# 1-Schematic_SmartPlugV2.net
KiCad netlist of a schematic drawn in EasyEDA
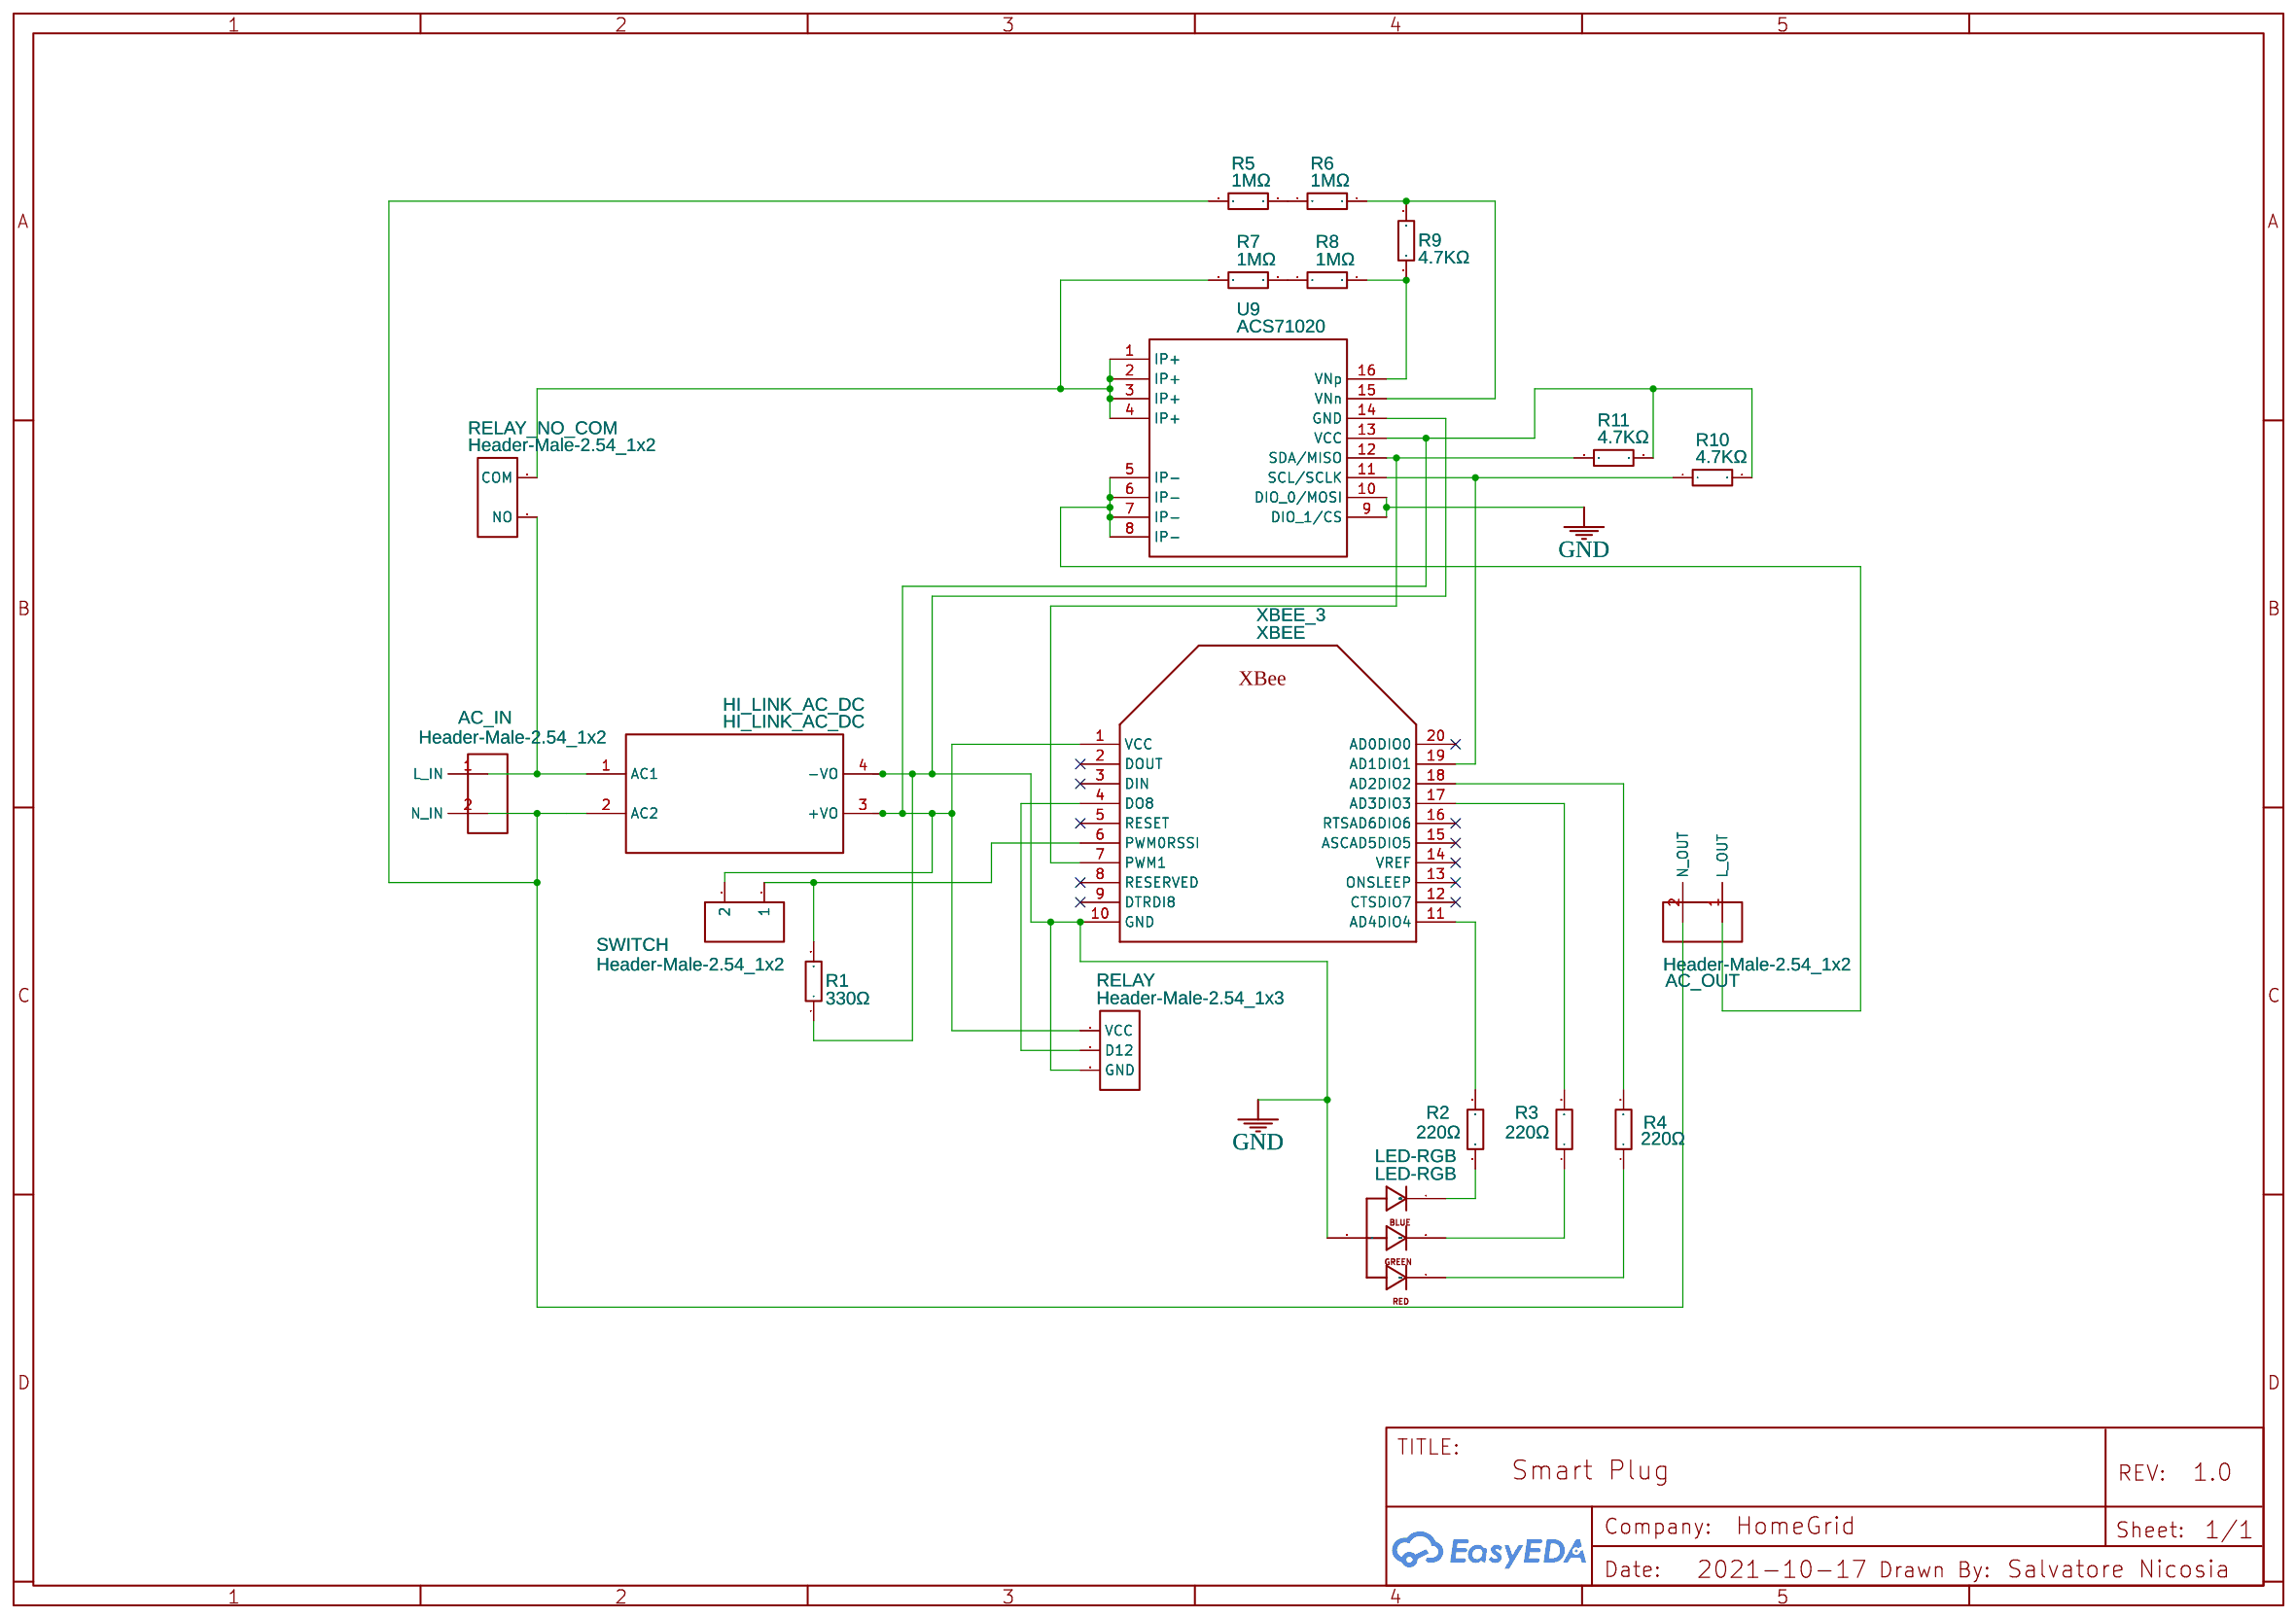
[diagram p0: schematic sheet]

(export (version "E")
  (design (tool "Eeschema 10.0.6"))
  (components
    (comp (ref "AC_IN") (value "Header-Male-2.54_1x2") (libsource (lib "") (part "DC Terminals (2)_1")))
    (comp (ref "AC_OUT") (value "Header-Male-2.54_1x2") (libsource (lib "") (part "DC Terminals (2)")))
    (comp (ref "HI_LINK_AC_DC") (value "HI_LINK_AC_DC") (libsource (lib "") (part "HI_LINK_AC_DC")))
    (comp (ref "LED-RGB") (value "LED-RGB") (libsource (lib "") (part "LED-RGB-CA-THRUCLEAR")))
    (comp (ref "R1") (value "330Ω") (libsource (lib "") (part "resistor 1k_2")))
    (comp (ref "R2") (value "220Ω") (libsource (lib "") (part "resistor 1k_2")))
    (comp (ref "R3") (value "220Ω") (libsource (lib "") (part "resistor 1k_2")))
    (comp (ref "R4") (value "220Ω") (libsource (lib "") (part "resistor 1k_2")))
    (comp (ref "R5") (value "1MΩ") (libsource (lib "") (part "resistor 1k")))
    (comp (ref "R6") (value "1MΩ") (libsource (lib "") (part "resistor 1k")))
    (comp (ref "R7") (value "1MΩ") (libsource (lib "") (part "resistor 1k")))
    (comp (ref "R8") (value "1MΩ") (libsource (lib "") (part "resistor 1k")))
    (comp (ref "R9") (value "4.7KΩ") (libsource (lib "") (part "resistor 1k_2")))
    (comp (ref "R10") (value "4.7KΩ") (libsource (lib "") (part "resistor 1k_1")))
    (comp (ref "R11") (value "4.7KΩ") (libsource (lib "") (part "resistor 1k_1")))
    (comp (ref "RELAY")
      (value "Header-Male-2.54_1x3")
      (fields
        (field (name "BOM_Manufacturer Part") "Header2.54mm 1*3P")
        (field (name "BOM_Supplier Part") "C49257")
      )
      (libsource (lib "") (part "Header-Male-2.54_1x3"))
    )
    (comp (ref "RELAY_NO_COM")
      (value "Header-Male-2.54_1x2")
      (fields (field (name "BOM_Manufacturer Part") "826629-2") (field (name "BOM_Supplier Part") "C86471"))
      (libsource (lib "") (part "Header-Male-2.54_1x2"))
    )
    (comp (ref "SWITCH")
      (value "Header-Male-2.54_1x2")
      (fields (field (name "BOM_Manufacturer Part") "826629-2") (field (name "BOM_Supplier Part") "C86471"))
      (libsource (lib "") (part "Header-Male-2.54_1x2_1"))
    )
    (comp (ref "U9")
      (value "ACS71020")
      (fields
        (field (name "BOM_Manufacturer Part") "ACS71020KMABTR-090B3-I2C")
        (field (name "BOM_Supplier Part") "620-1998-1-ND")
      )
      (libsource (lib "") (part "ACS71020"))
    )
    (comp (ref "XBEE_3") (value "XBEE") (libsource (lib "") (part "XBEE")))
  )
  (nets
    (net (code "1") (name "GND") (class "Default")
      (node (ref "HI_LINK_AC_DC") (pin "4") (pinfunction "-VO_4") (pintype "unspecified"))
      (node (ref "LED-RGB") (pin "2") (pinfunction "ANODE_2") (pintype "unspecified"))
      (node (ref "R1") (pin "1") (pinfunction "1_1") (pintype "unspecified"))
      (node (ref "RELAY") (pin "3") (pinfunction "GND_3") (pintype "input"))
      (node (ref "U9") (pin "10") (pinfunction "DIO_0/MOSI_10") (pintype "unspecified"))
      (node (ref "U9") (pin "14") (pinfunction "GND_14") (pintype "unspecified"))
      (node (ref "U9") (pin "9") (pinfunction "DIO_1/CS_9") (pintype "unspecified"))
      (node (ref "XBEE_3") (pin "10") (pinfunction "GND_10") (pintype "unspecified"))
    )
    (net (code "2") (name "Net-(AC_IN-L_IN)") (class "Default")
      (node (ref "AC_IN") (pin "1") (pinfunction "L_IN_1") (pintype "unspecified"))
      (node (ref "HI_LINK_AC_DC") (pin "1") (pinfunction "AC1_1") (pintype "unspecified"))
      (node (ref "RELAY_NO_COM") (pin "1") (pinfunction "NO_1") (pintype "unspecified"))
    )
    (net (code "3") (name "Net-(AC_IN-N_IN)") (class "Default")
      (node (ref "AC_IN") (pin "2") (pinfunction "N_IN_2") (pintype "unspecified"))
      (node (ref "AC_OUT") (pin "2") (pinfunction "N_OUT_2") (pintype "unspecified"))
      (node (ref "HI_LINK_AC_DC") (pin "2") (pinfunction "AC2_2") (pintype "unspecified"))
      (node (ref "R5") (pin "2") (pinfunction "2_2") (pintype "unspecified"))
    )
    (net (code "4") (name "Net-(AC_OUT-L_OUT)") (class "Default")
      (node (ref "AC_OUT") (pin "1") (pinfunction "L_OUT_1") (pintype "unspecified"))
      (node (ref "U9") (pin "5") (pinfunction "IP-_5") (pintype "unspecified"))
      (node (ref "U9") (pin "6") (pinfunction "IP-_6") (pintype "unspecified"))
      (node (ref "U9") (pin "7") (pinfunction "IP-_7") (pintype "unspecified"))
      (node (ref "U9") (pin "8") (pinfunction "IP-_8") (pintype "unspecified"))
    )
    (net (code "5") (name "Net-(HI_LINK_AC_DC-+VO)") (class "Default")
      (node (ref "HI_LINK_AC_DC") (pin "3") (pinfunction "+VO_3") (pintype "unspecified"))
      (node (ref "R10") (pin "2") (pinfunction "2_2") (pintype "unspecified"))
      (node (ref "R11") (pin "2") (pinfunction "2_2") (pintype "unspecified"))
      (node (ref "RELAY") (pin "1") (pinfunction "VCC_1") (pintype "input"))
      (node (ref "SWITCH") (pin "2") (pinfunction "2_2") (pintype "unspecified"))
      (node (ref "U9") (pin "13") (pinfunction "VCC_13") (pintype "unspecified"))
      (node (ref "XBEE_3") (pin "1") (pinfunction "VCC_1") (pintype "unspecified"))
    )
    (net (code "6") (name "Net-(LED-RGB-BLUE_CATHODE)") (class "Default")
      (node (ref "LED-RGB") (pin "4") (pinfunction "BLUE_CATHODE_4") (pintype "unspecified"))
      (node (ref "R2") (pin "1") (pinfunction "1_1") (pintype "unspecified"))
    )
    (net (code "7") (name "Net-(LED-RGB-GREEN_CATHODE)") (class "Default")
      (node (ref "LED-RGB") (pin "3") (pinfunction "GREEN_CATHODE_3") (pintype "unspecified"))
      (node (ref "R3") (pin "1") (pinfunction "1_1") (pintype "unspecified"))
    )
    (net (code "8") (name "Net-(LED-RGB-RED_CATHODE)") (class "Default")
      (node (ref "LED-RGB") (pin "1") (pinfunction "RED_CATHODE_1") (pintype "unspecified"))
      (node (ref "R4") (pin "1") (pinfunction "1_1") (pintype "unspecified"))
    )
    (net (code "9") (name "Net-(R5-Pad1)") (class "Default")
      (node (ref "R5") (pin "1") (pinfunction "1_1") (pintype "unspecified"))
      (node (ref "R6") (pin "2") (pinfunction "2_2") (pintype "unspecified"))
    )
    (net (code "10") (name "Net-(R7-Pad1)") (class "Default")
      (node (ref "R7") (pin "1") (pinfunction "1_1") (pintype "unspecified"))
      (node (ref "R8") (pin "2") (pinfunction "2_2") (pintype "unspecified"))
    )
    (net (code "11") (name "Net-(RELAY-D12)") (class "Default")
      (node (ref "RELAY") (pin "2") (pinfunction "D12_2") (pintype "input"))
      (node (ref "XBEE_3") (pin "4") (pinfunction "DO8_4") (pintype "output"))
    )
    (net (code "12") (name "Net-(RELAY_NO_COM-COM)") (class "Default")
      (node (ref "R7") (pin "2") (pinfunction "2_2") (pintype "unspecified"))
      (node (ref "RELAY_NO_COM") (pin "2") (pinfunction "COM_2") (pintype "unspecified"))
      (node (ref "U9") (pin "1") (pinfunction "IP+_1") (pintype "unspecified"))
      (node (ref "U9") (pin "2") (pinfunction "IP+_2") (pintype "unspecified"))
      (node (ref "U9") (pin "3") (pinfunction "IP+_3") (pintype "unspecified"))
      (node (ref "U9") (pin "4") (pinfunction "IP+_4") (pintype "unspecified"))
    )
    (net (code "13") (name "Net-(U9-SCL{slash}SCLK)") (class "Default")
      (node (ref "R10") (pin "1") (pinfunction "1_1") (pintype "unspecified"))
      (node (ref "U9") (pin "11") (pinfunction "SCL/SCLK_11") (pintype "unspecified"))
      (node (ref "XBEE_3") (pin "19") (pinfunction "AD1DIO1_19") (pintype "unspecified"))
    )
    (net (code "14") (name "Net-(U9-SDA{slash}MISO)") (class "Default")
      (node (ref "R11") (pin "1") (pinfunction "1_1") (pintype "unspecified"))
      (node (ref "U9") (pin "12") (pinfunction "SDA/MISO_12") (pintype "unspecified"))
      (node (ref "XBEE_3") (pin "7") (pinfunction "PWM1_7") (pintype "output"))
    )
    (net (code "15") (name "Net-(U9-VNn)") (class "Default")
      (node (ref "R6") (pin "1") (pinfunction "1_1") (pintype "unspecified"))
      (node (ref "R9") (pin "2") (pinfunction "2_2") (pintype "unspecified"))
      (node (ref "U9") (pin "15") (pinfunction "VNn_15") (pintype "unspecified"))
    )
    (net (code "16") (name "Net-(U9-VNp)") (class "Default")
      (node (ref "R8") (pin "1") (pinfunction "1_1") (pintype "unspecified"))
      (node (ref "R9") (pin "1") (pinfunction "1_1") (pintype "unspecified"))
      (node (ref "U9") (pin "16") (pinfunction "VNp_16") (pintype "unspecified"))
    )
    (net (code "17") (name "Net-(XBEE_3-AD2DIO2)") (class "Default")
      (node (ref "R4") (pin "2") (pinfunction "2_2") (pintype "unspecified"))
      (node (ref "XBEE_3") (pin "18") (pinfunction "AD2DIO2_18") (pintype "unspecified"))
    )
    (net (code "18") (name "Net-(XBEE_3-AD3DIO3)") (class "Default")
      (node (ref "R3") (pin "2") (pinfunction "2_2") (pintype "unspecified"))
      (node (ref "XBEE_3") (pin "17") (pinfunction "AD3DIO3_17") (pintype "unspecified"))
    )
    (net (code "19") (name "Net-(XBEE_3-AD4DIO4)") (class "Default")
      (node (ref "R2") (pin "2") (pinfunction "2_2") (pintype "unspecified"))
      (node (ref "XBEE_3") (pin "11") (pinfunction "AD4DIO4_11") (pintype "unspecified"))
    )
    (net (code "20") (name "Net-(XBEE_3-PWM0RSSI)") (class "Default")
      (node (ref "R1") (pin "2") (pinfunction "2_2") (pintype "unspecified"))
      (node (ref "SWITCH") (pin "1") (pinfunction "1_1") (pintype "unspecified"))
      (node (ref "XBEE_3") (pin "6") (pinfunction "PWM0RSSI_6") (pintype "output"))
    )
    (net (code "21") (name "unconnected-(XBEE_3-AD0DIO0-Pad20)") (class "Default")
      (node (ref "XBEE_3") (pin "20") (pinfunction "AD0DIO0_20") (pintype "unspecified+no_connect"))
    )
    (net (code "22") (name "unconnected-(XBEE_3-ASCAD5DIO5-Pad15)") (class "Default")
      (node (ref "XBEE_3") (pin "15") (pinfunction "ASCAD5DIO5_15") (pintype "unspecified+no_connect"))
    )
    (net (code "23") (name "unconnected-(XBEE_3-CTSDIO7-Pad12)") (class "Default")
      (node (ref "XBEE_3") (pin "12") (pinfunction "CTSDIO7_12") (pintype "unspecified+no_connect"))
    )
    (net (code "24") (name "unconnected-(XBEE_3-DIN-Pad3)") (class "Default")
      (node (ref "XBEE_3") (pin "3") (pinfunction "DIN_3") (pintype "input+no_connect"))
    )
    (net (code "25") (name "unconnected-(XBEE_3-DOUT-Pad2)") (class "Default")
      (node (ref "XBEE_3") (pin "2") (pinfunction "DOUT_2") (pintype "output+no_connect"))
    )
    (net (code "26") (name "unconnected-(XBEE_3-DTRDI8-Pad9)") (class "Default")
      (node (ref "XBEE_3") (pin "9") (pinfunction "DTRDI8_9") (pintype "input+no_connect"))
    )
    (net (code "27") (name "unconnected-(XBEE_3-ONSLEEP-Pad13)") (class "Default")
      (node (ref "XBEE_3") (pin "13") (pinfunction "ONSLEEP_13") (pintype "output+no_connect"))
    )
    (net (code "28") (name "unconnected-(XBEE_3-RESERVED-Pad8)") (class "Default")
      (node (ref "XBEE_3") (pin "8") (pinfunction "RESERVED_8") (pintype "unspecified+no_connect"))
    )
    (net (code "29") (name "unconnected-(XBEE_3-RESET-Pad5)") (class "Default")
      (node (ref "XBEE_3") (pin "5") (pinfunction "RESET_5") (pintype "input+no_connect"))
    )
    (net (code "30") (name "unconnected-(XBEE_3-RTSAD6DIO6-Pad16)") (class "Default")
      (node (ref "XBEE_3") (pin "16") (pinfunction "RTSAD6DIO6_16") (pintype "unspecified+no_connect"))
    )
    (net (code "31") (name "unconnected-(XBEE_3-VREF-Pad14)") (class "Default")
      (node (ref "XBEE_3") (pin "14") (pinfunction "VREF_14") (pintype "input+no_connect"))
    )
  )
)
